# ESP32.net
KiCad netlist of a schematic drawn in Altium Designer
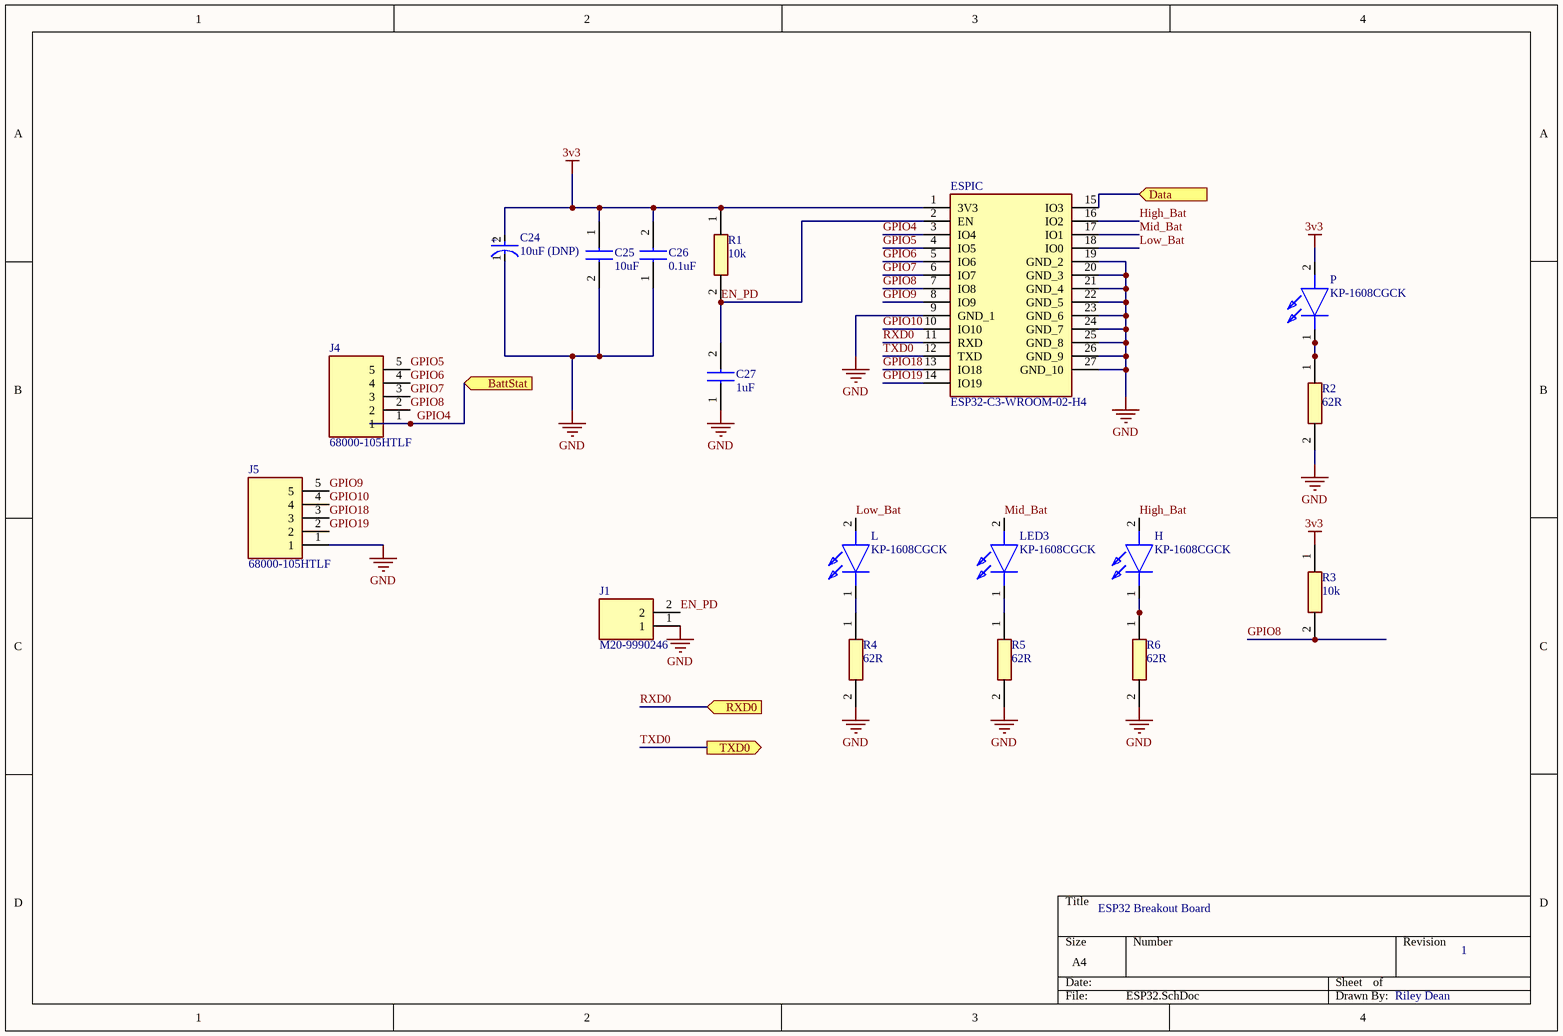
[diagram p0: ESP32.SchDoc]

(export (version "E")
  (design (tool "Eeschema 10.0.6"))
  (components
    (comp (ref "C24")
      (value "10uF (DNP)")
      (footprint "FP-TAJS-MFG")
      (description "10uF 2.5V  ±10% 8Ω 1206  SMD Tantalum Capacitor, TAJS106K002RNJ")
      (fields (field (name "TOLERANCE") "10%") (field (name "VOLTAGE") "2.5V"))
      (libsource (lib "Altium Content Vault") (part "a00bbbee19879c290e62620ae7e47b1"))
    )
    (comp (ref "C25")
      (value "10uF")
      (footprint "SamacSys:CAPC1608X90N")
      (description "Capacitor, CL10A106MQ8NNNC")
      (fields
        (field (name "MANUFACTURER_PART_NUMBER") "CL10A106MQ8NNNC")
        (field (name "MOUSER PART NUMBER") "187-CL10A106MQ8NNNC")
      )
      (libsource (lib "*") (part "CL10A106MQ8NNNC"))
    )
    (comp (ref "C26")
      (value "0.1uF")
      (footprint "SamacSys:CAPC3216X180N")
      (description "Capacitor, GCM31C5C1H104FA16L, 1206")
      (fields
        (field (name "MANUFACTURER_PART_NUMBER") "GCM31C5C1H104FA16L")
        (field (name "MOUSER PART NUMBER") "81-GCM31C5C1H104FA16")
      )
      (libsource (lib "*") (part "GCM31C5C1H104FA16L"))
    )
    (comp (ref "C27")
      (value "1uF")
      (footprint "SamacSys:CAPC1608X90N")
      (description "Capacitor, 0603YC10JAT2A")
      (fields
        (field (name "MANUFACTURER_PART_NUMBER") "0603YC105JAT2A")
        (field (name "MOUSER PART NUMBER") "581-0603YC105JAT2A")
      )
      (libsource (lib "*") (part "0603YC105JAT2A"))
    )
    (comp (ref "ESPIC")
      (value "ESP32-C3-WROOM-02-H4")
      (footprint "SamacSys:ESP32C3WROOM02H4")
      (description "Integrated Circuit")
      (fields (field (name "MOUSER PART NUMBER") "356-ESP32C3WROOM02H4"))
      (libsource (lib "*") (part "ESP32-C3-WROOM-02-H4"))
    )
    (comp (ref "H")
      (value "KP-1608CGCK")
      (footprint "SamacSys:LEDC1608X120N")
      (description "LED")
      (libsource (lib "*") (part "KP-1608CGCK"))
    )
    (comp (ref "J1")
      (value "M20-9990246")
      (footprint "SamacSys:HDRV2W66P0X254_1X2_508X254X874P")
      (description "Connector")
      (fields (field (name "MOUSER PART NUMBER") "855-M20-9990246"))
      (libsource (lib "*") (part "M20-9990246"))
    )
    (comp (ref "J4")
      (value "68000-105HTLF")
      (footprint "SamacSys:HDRV5W67P0X254_1X5_1270X241X858P")
      (description "Connector")
      (fields (field (name "MOUSER PART NUMBER") "649-68000-105HTLF"))
      (libsource (lib "*") (part "68000-105HTLF"))
    )
    (comp (ref "J5")
      (value "68000-105HTLF")
      (footprint "SamacSys:HDRV5W67P0X254_1X5_1270X241X858P")
      (description "Connector")
      (fields (field (name "MOUSER PART NUMBER") "649-68000-105HTLF"))
      (libsource (lib "*") (part "68000-105HTLF"))
    )
    (comp (ref "L")
      (value "KP-1608CGCK")
      (footprint "SamacSys:LEDC1608X120N")
      (description "LED")
      (libsource (lib "*") (part "KP-1608CGCK"))
    )
    (comp (ref "LED3")
      (value "KP-1608CGCK")
      (footprint "SamacSys:LEDC1608X120N")
      (description "LED")
      (libsource (lib "*") (part "KP-1608CGCK"))
    )
    (comp (ref "P")
      (value "KP-1608CGCK")
      (footprint "SamacSys:LEDC1608X120N")
      (description "LED")
      (libsource (lib "*") (part "KP-1608CGCK"))
    )
    (comp (ref "R1")
      (value "10k")
      (footprint "SamacSys:RESC2012X60N")
      (description "Resistor, RC0805FR-7W10KL, 10k")
      (fields
        (field (name "MANUFACTURER_PART_NUMBER") "RC0805FR-7W10KL")
        (field (name "MOUSER PART NUMBER") "603-RC0805FR-7W10KL")
      )
      (libsource (lib "*") (part "RC0805FR-7W10KL"))
    )
    (comp (ref "R2")
      (value "62R")
      (footprint "SamacSys:ERJH3")
      (description "Resistor, ERJ-H3EF62R0V, 62ohms")
      (fields (field (name "MANUFACTURER_PART_NUMBER") "ERJ-H3EF62R0V"))
      (libsource (lib "*") (part "ERJ-H3EF62R0V"))
    )
    (comp (ref "R3")
      (value "10k")
      (footprint "SamacSys:RESC2012X60N")
      (description "Resistor, RC0805FR-7W10KL, 10k")
      (fields
        (field (name "MANUFACTURER_PART_NUMBER") "RC0805FR-7W10KL")
        (field (name "MOUSER PART NUMBER") "603-RC0805FR-7W10KL")
      )
      (libsource (lib "*") (part "RC0805FR-7W10KL"))
    )
    (comp (ref "R4")
      (value "62R")
      (footprint "SamacSys:ERJH3")
      (description "Resistor, ERJ-H3EF62R0V, 62ohms")
      (fields (field (name "MANUFACTURER_PART_NUMBER") "ERJ-H3EF62R0V"))
      (libsource (lib "*") (part "ERJ-H3EF62R0V"))
    )
    (comp (ref "R5")
      (value "62R")
      (footprint "SamacSys:ERJH3")
      (description "Resistor, ERJ-H3EF62R0V, 62ohms")
      (fields (field (name "MANUFACTURER_PART_NUMBER") "ERJ-H3EF62R0V"))
      (libsource (lib "*") (part "ERJ-H3EF62R0V"))
    )
    (comp (ref "R6")
      (value "62R")
      (footprint "SamacSys:ERJH3")
      (description "Resistor, ERJ-H3EF62R0V, 62ohms")
      (fields (field (name "MANUFACTURER_PART_NUMBER") "ERJ-H3EF62R0V"))
      (libsource (lib "*") (part "ERJ-H3EF62R0V"))
    )
  )
  (nets
    (net (code "1") (name "/Data") (class "Default")
      (node (ref "ESPIC") (pin "15") (pinfunction "IO3_15") (pintype "passive"))
    )
    (net (code "2") (name "/EN_PD") (class "Default")
      (node (ref "C27") (pin "2") (pinfunction "2_2") (pintype "passive"))
      (node (ref "ESPIC") (pin "2") (pinfunction "EN_2") (pintype "passive"))
      (node (ref "J1") (pin "2") (pinfunction "2_2") (pintype "passive"))
      (node (ref "R1") (pin "2") (pinfunction "2_2") (pintype "passive"))
    )
    (net (code "3") (name "/GPIO4") (class "Default")
      (node (ref "ESPIC") (pin "3") (pinfunction "IO4_3") (pintype "passive"))
      (node (ref "J4") (pin "1") (pinfunction "1_1") (pintype "passive"))
    )
    (net (code "4") (name "/GPIO5") (class "Default")
      (node (ref "ESPIC") (pin "4") (pinfunction "IO5_4") (pintype "passive"))
      (node (ref "J4") (pin "5") (pinfunction "5_5") (pintype "passive"))
    )
    (net (code "5") (name "/GPIO6") (class "Default")
      (node (ref "ESPIC") (pin "5") (pinfunction "IO6_5") (pintype "passive"))
      (node (ref "J4") (pin "4") (pinfunction "4_4") (pintype "passive"))
    )
    (net (code "6") (name "/GPIO7") (class "Default")
      (node (ref "ESPIC") (pin "6") (pinfunction "IO7_6") (pintype "passive"))
      (node (ref "J4") (pin "3") (pinfunction "3_3") (pintype "passive"))
    )
    (net (code "7") (name "/GPIO8") (class "Default")
      (node (ref "ESPIC") (pin "7") (pinfunction "IO8_7") (pintype "passive"))
      (node (ref "J4") (pin "2") (pinfunction "2_2") (pintype "passive"))
      (node (ref "R3") (pin "2") (pinfunction "2_2") (pintype "passive"))
    )
    (net (code "8") (name "/GPIO9") (class "Default")
      (node (ref "ESPIC") (pin "8") (pinfunction "IO9_8") (pintype "passive"))
      (node (ref "J5") (pin "5") (pinfunction "5_5") (pintype "passive"))
    )
    (net (code "9") (name "/GPIO10") (class "Default")
      (node (ref "ESPIC") (pin "10") (pinfunction "IO10_10") (pintype "passive"))
      (node (ref "J5") (pin "4") (pinfunction "4_4") (pintype "passive"))
    )
    (net (code "10") (name "/GPIO18") (class "Default")
      (node (ref "ESPIC") (pin "13") (pinfunction "IO18_13") (pintype "passive"))
      (node (ref "J5") (pin "3") (pinfunction "3_3") (pintype "passive"))
    )
    (net (code "11") (name "/GPIO19") (class "Default")
      (node (ref "ESPIC") (pin "14") (pinfunction "IO19_14") (pintype "passive"))
      (node (ref "J5") (pin "2") (pinfunction "2_2") (pintype "passive"))
    )
    (net (code "12") (name "/High_Bat") (class "Default")
      (node (ref "ESPIC") (pin "16") (pinfunction "IO2_16") (pintype "passive"))
      (node (ref "H") (pin "2") (pinfunction "A_2") (pintype "passive"))
    )
    (net (code "13") (name "/Low_Bat") (class "Default")
      (node (ref "ESPIC") (pin "18") (pinfunction "IO0_18") (pintype "passive"))
      (node (ref "L") (pin "2") (pinfunction "A_2") (pintype "passive"))
    )
    (net (code "14") (name "/Mid_Bat") (class "Default")
      (node (ref "ESPIC") (pin "17") (pinfunction "IO1_17") (pintype "passive"))
      (node (ref "LED3") (pin "2") (pinfunction "A_2") (pintype "passive"))
    )
    (net (code "15") (name "/RXD0") (class "Default")
      (node (ref "ESPIC") (pin "11") (pinfunction "RXD_11") (pintype "passive"))
    )
    (net (code "16") (name "/TXD0") (class "Default")
      (node (ref "ESPIC") (pin "12") (pinfunction "TXD_12") (pintype "passive"))
    )
    (net (code "17") (name "3v3") (class "Default")
      (node (ref "C24") (pin "2") (pinfunction "A_2") (pintype "passive"))
      (node (ref "C25") (pin "1") (pinfunction "1_1") (pintype "passive"))
      (node (ref "C26") (pin "2") (pinfunction "2_2") (pintype "passive"))
      (node (ref "ESPIC") (pin "1") (pinfunction "3V3_1") (pintype "passive"))
      (node (ref "P") (pin "2") (pinfunction "A_2") (pintype "passive"))
      (node (ref "R1") (pin "1") (pinfunction "1_1") (pintype "passive"))
      (node (ref "R3") (pin "1") (pinfunction "1_1") (pintype "passive"))
    )
    (net (code "18") (name "GND") (class "Default")
      (node (ref "C24") (pin "1") (pinfunction "C_1") (pintype "passive"))
      (node (ref "C25") (pin "2") (pinfunction "2_2") (pintype "passive"))
      (node (ref "C26") (pin "1") (pinfunction "1_1") (pintype "passive"))
      (node (ref "C27") (pin "1") (pinfunction "1_1") (pintype "passive"))
      (node (ref "ESPIC") (pin "19") (pinfunction "GND_2_19") (pintype "passive"))
      (node (ref "ESPIC") (pin "20") (pinfunction "GND_3_20") (pintype "passive"))
      (node (ref "ESPIC") (pin "21") (pinfunction "GND_4_21") (pintype "passive"))
      (node (ref "ESPIC") (pin "22") (pinfunction "GND_5_22") (pintype "passive"))
      (node (ref "ESPIC") (pin "23") (pinfunction "GND_6_23") (pintype "passive"))
      (node (ref "ESPIC") (pin "24") (pinfunction "GND_7_24") (pintype "passive"))
      (node (ref "ESPIC") (pin "25") (pinfunction "GND_8_25") (pintype "passive"))
      (node (ref "ESPIC") (pin "26") (pinfunction "GND_9_26") (pintype "passive"))
      (node (ref "ESPIC") (pin "27") (pinfunction "GND_10_27") (pintype "passive"))
      (node (ref "ESPIC") (pin "9") (pinfunction "GND_1_9") (pintype "passive"))
      (node (ref "J1") (pin "1") (pinfunction "1_1") (pintype "passive"))
      (node (ref "J5") (pin "1") (pinfunction "1_1") (pintype "passive"))
      (node (ref "R2") (pin "2") (pinfunction "2_2") (pintype "passive"))
      (node (ref "R4") (pin "2") (pinfunction "2_2") (pintype "passive"))
      (node (ref "R5") (pin "2") (pinfunction "2_2") (pintype "passive"))
      (node (ref "R6") (pin "2") (pinfunction "2_2") (pintype "passive"))
    )
    (net (code "19") (name "Net-(H-K)") (class "Default")
      (node (ref "H") (pin "1") (pinfunction "K_1") (pintype "passive"))
      (node (ref "R6") (pin "1") (pinfunction "1_1") (pintype "passive"))
    )
    (net (code "20") (name "Net-(L-K)") (class "Default")
      (node (ref "L") (pin "1") (pinfunction "K_1") (pintype "passive"))
      (node (ref "R4") (pin "1") (pinfunction "1_1") (pintype "passive"))
    )
    (net (code "21") (name "Net-(LED3-K)") (class "Default")
      (node (ref "LED3") (pin "1") (pinfunction "K_1") (pintype "passive"))
      (node (ref "R5") (pin "1") (pinfunction "1_1") (pintype "passive"))
    )
    (net (code "22") (name "Net-(P-K)") (class "Default")
      (node (ref "P") (pin "1") (pinfunction "K_1") (pintype "passive"))
      (node (ref "R2") (pin "1") (pinfunction "1_1") (pintype "passive"))
    )
  )
)
